# 3_DAC_schdoc.net
KiCad netlist of a schematic drawn in Altium Designer
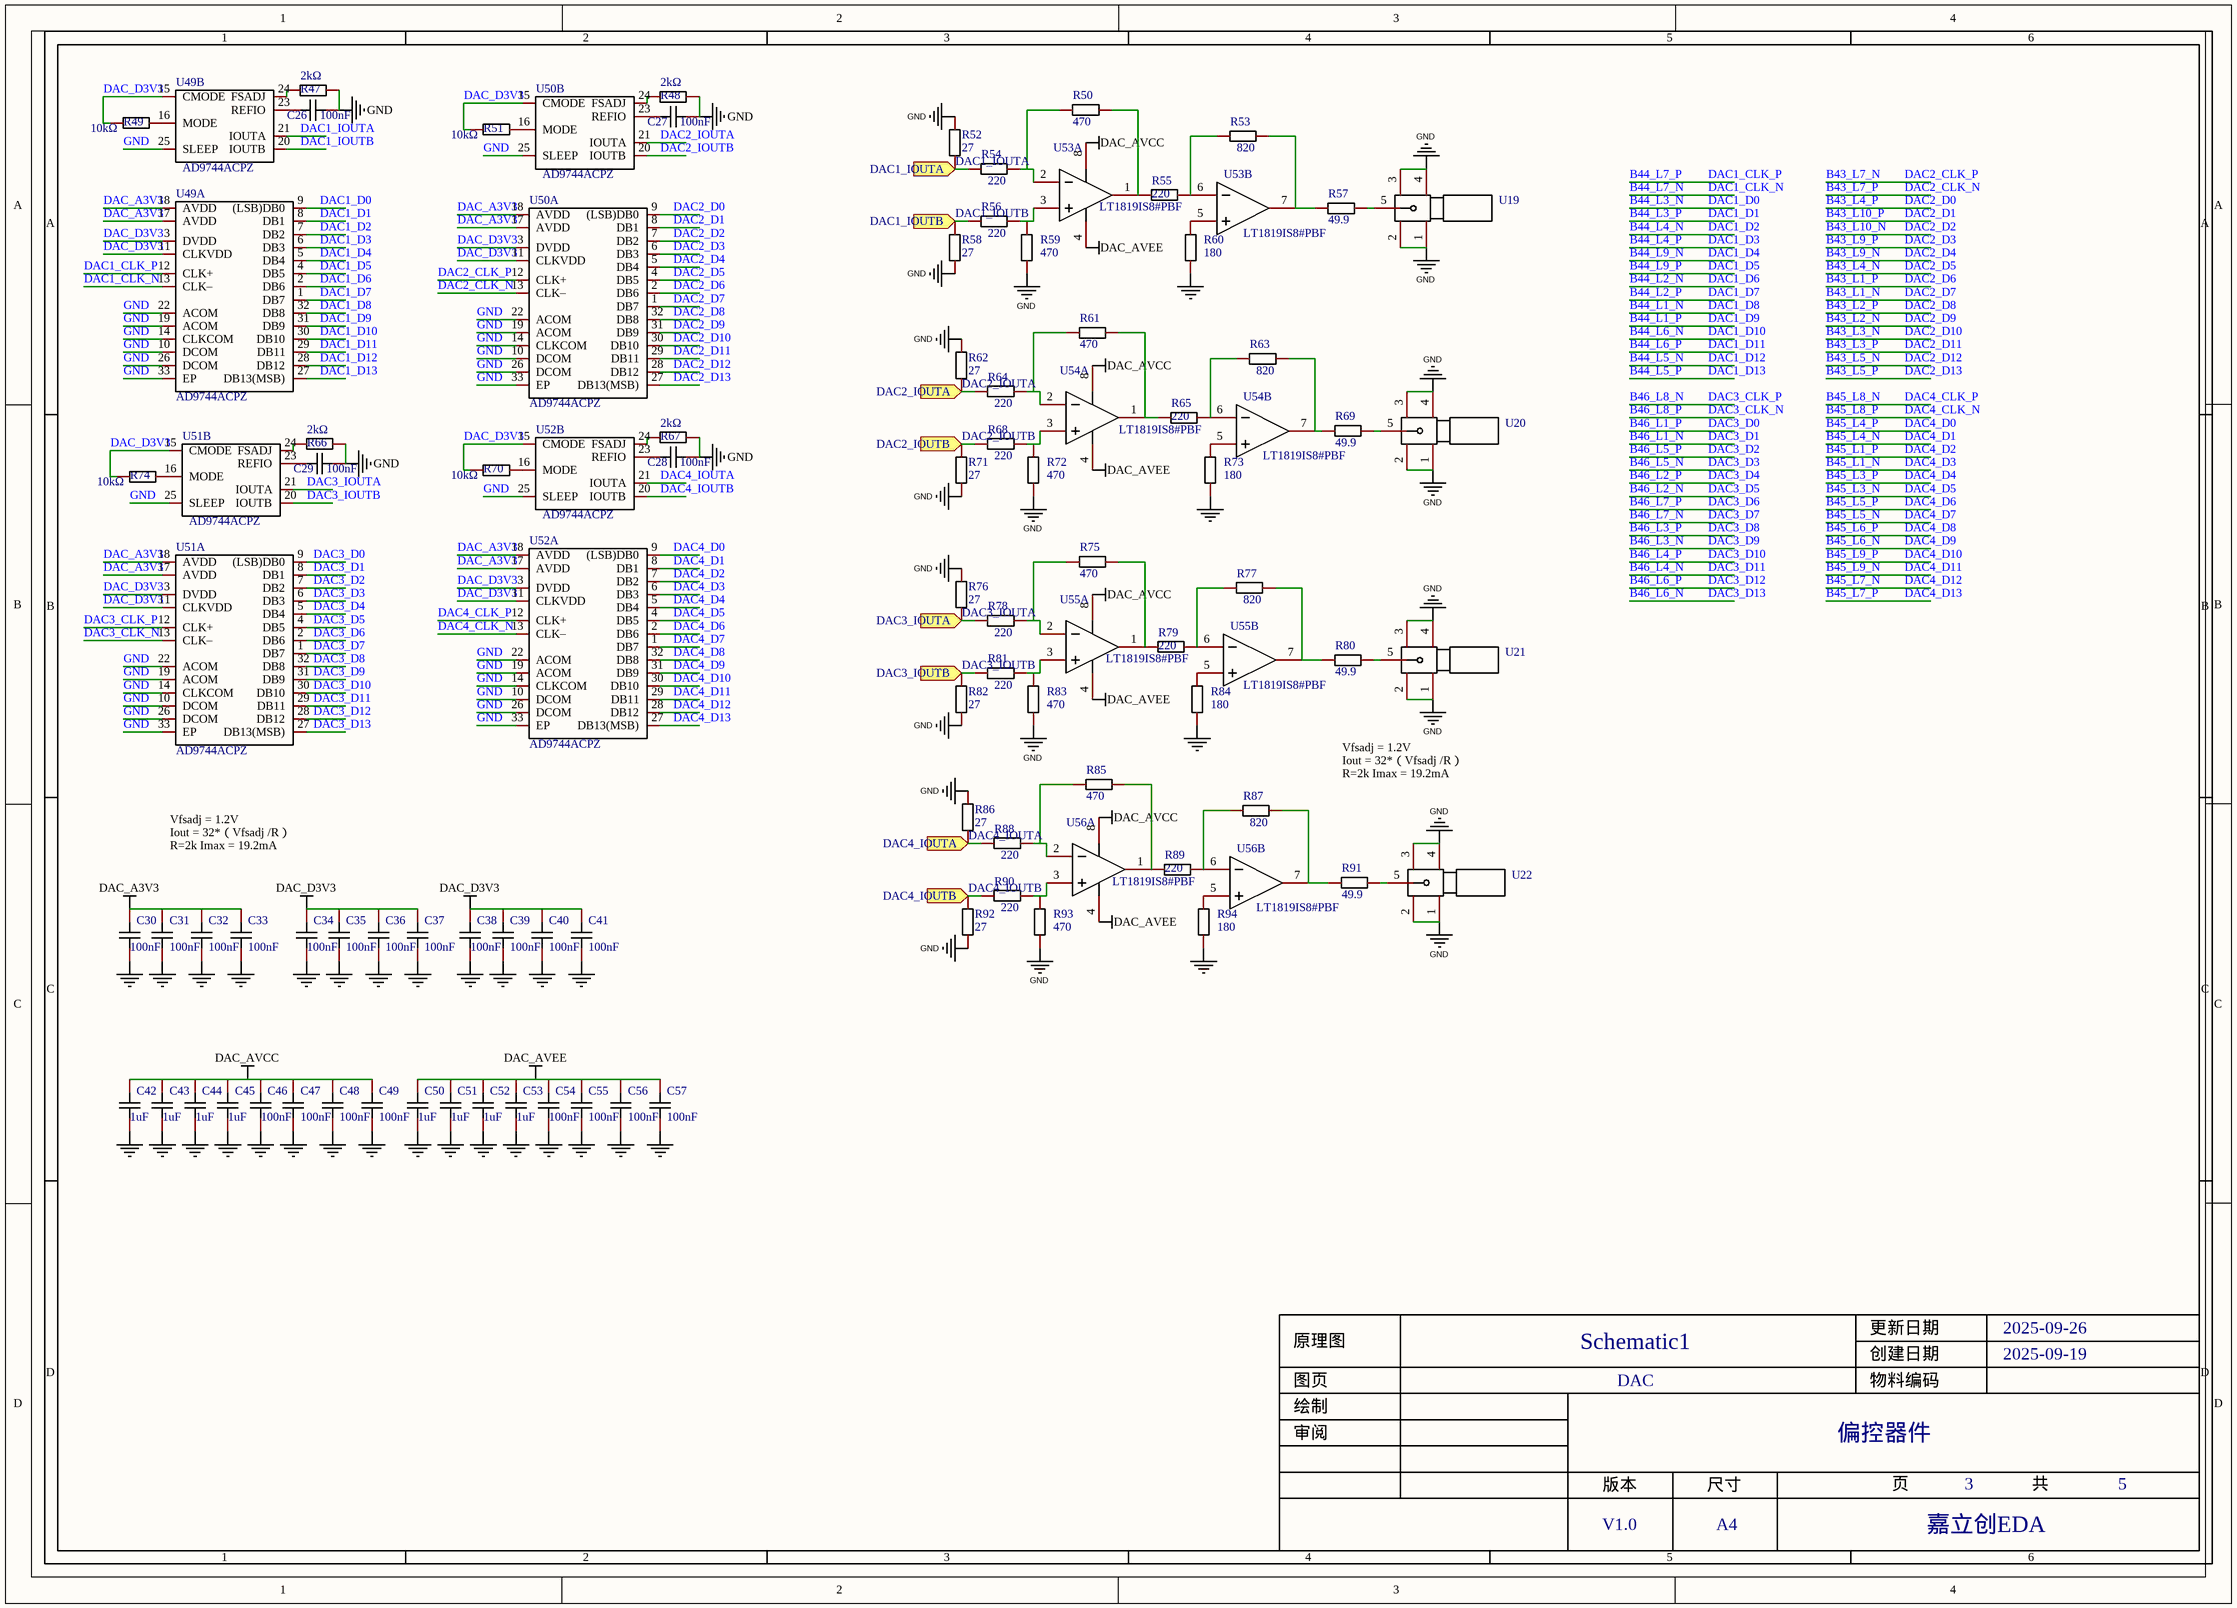
[diagram p0: 3_DAC.schdoc.schdoc]

(export (version "E")
  (design (tool "Eeschema 10.0.6"))
  (components
    (comp (ref "C26")
      (value "100nF")
      (fields
        (field (name "NAME") "100nF")
        (field (name "MANUFACTURER") "muRata(村田)")
        (field (name "MANUFACTURER PART") "GRM155R71H104KE14D")
        (field (name "TOLERANCE") "±10%")
      )
      (libsource (lib "altium-import") (part "root_0_GRM155R71H104KE14D_"))
    )
    (comp (ref "C27")
      (value "100nF")
      (fields
        (field (name "NAME") "100nF")
        (field (name "MANUFACTURER") "muRata(村田)")
        (field (name "MANUFACTURER PART") "GRM155R71H104KE14D")
        (field (name "TOLERANCE") "±10%")
      )
      (libsource (lib "altium-import") (part "root_0_GRM155R71H104KE14D_"))
    )
    (comp (ref "C28")
      (value "100nF")
      (fields
        (field (name "NAME") "100nF")
        (field (name "MANUFACTURER") "muRata(村田)")
        (field (name "MANUFACTURER PART") "GRM155R71H104KE14D")
        (field (name "TOLERANCE") "±10%")
      )
      (libsource (lib "altium-import") (part "root_0_GRM155R71H104KE14D_"))
    )
    (comp (ref "C29")
      (value "100nF")
      (fields
        (field (name "NAME") "100nF")
        (field (name "MANUFACTURER") "muRata(村田)")
        (field (name "MANUFACTURER PART") "GRM155R71H104KE14D")
        (field (name "TOLERANCE") "±10%")
      )
      (libsource (lib "altium-import") (part "root_0_GRM155R71H104KE14D_"))
    )
    (comp (ref "C30")
      (value "100nF")
      (fields
        (field (name "NAME") "100nF")
        (field (name "MANUFACTURER") "muRata(村田)")
        (field (name "MANUFACTURER PART") "GRM155R71H104KE14D")
        (field (name "TOLERANCE") "±10%")
      )
      (libsource (lib "altium-import") (part "root_1_GRM155R71H104KE14D_"))
    )
    (comp (ref "C31")
      (value "100nF")
      (fields
        (field (name "NAME") "100nF")
        (field (name "MANUFACTURER") "muRata(村田)")
        (field (name "MANUFACTURER PART") "GRM155R71H104KE14D")
        (field (name "TOLERANCE") "±10%")
      )
      (libsource (lib "altium-import") (part "root_1_GRM155R71H104KE14D_"))
    )
    (comp (ref "C32")
      (value "100nF")
      (fields
        (field (name "NAME") "100nF")
        (field (name "MANUFACTURER") "muRata(村田)")
        (field (name "MANUFACTURER PART") "GRM155R71H104KE14D")
        (field (name "TOLERANCE") "±10%")
      )
      (libsource (lib "altium-import") (part "root_1_GRM155R71H104KE14D_"))
    )
    (comp (ref "C33")
      (value "100nF")
      (fields
        (field (name "NAME") "100nF")
        (field (name "MANUFACTURER") "muRata(村田)")
        (field (name "MANUFACTURER PART") "GRM155R71H104KE14D")
        (field (name "TOLERANCE") "±10%")
      )
      (libsource (lib "altium-import") (part "root_1_GRM155R71H104KE14D_"))
    )
    (comp (ref "C34")
      (value "100nF")
      (fields
        (field (name "NAME") "100nF")
        (field (name "MANUFACTURER") "muRata(村田)")
        (field (name "MANUFACTURER PART") "GRM155R71H104KE14D")
        (field (name "TOLERANCE") "±10%")
      )
      (libsource (lib "altium-import") (part "root_1_GRM155R71H104KE14D_"))
    )
    (comp (ref "C35")
      (value "100nF")
      (fields
        (field (name "NAME") "100nF")
        (field (name "MANUFACTURER") "muRata(村田)")
        (field (name "MANUFACTURER PART") "GRM155R71H104KE14D")
        (field (name "TOLERANCE") "±10%")
      )
      (libsource (lib "altium-import") (part "root_1_GRM155R71H104KE14D_"))
    )
    (comp (ref "C36")
      (value "100nF")
      (fields
        (field (name "NAME") "100nF")
        (field (name "MANUFACTURER") "muRata(村田)")
        (field (name "MANUFACTURER PART") "GRM155R71H104KE14D")
        (field (name "TOLERANCE") "±10%")
      )
      (libsource (lib "altium-import") (part "root_1_GRM155R71H104KE14D_"))
    )
    (comp (ref "C37")
      (value "100nF")
      (fields
        (field (name "NAME") "100nF")
        (field (name "MANUFACTURER") "muRata(村田)")
        (field (name "MANUFACTURER PART") "GRM155R71H104KE14D")
        (field (name "TOLERANCE") "±10%")
      )
      (libsource (lib "altium-import") (part "root_1_GRM155R71H104KE14D_"))
    )
    (comp (ref "C38")
      (value "100nF")
      (fields
        (field (name "NAME") "100nF")
        (field (name "MANUFACTURER") "muRata(村田)")
        (field (name "MANUFACTURER PART") "GRM155R71H104KE14D")
        (field (name "TOLERANCE") "±10%")
      )
      (libsource (lib "altium-import") (part "root_1_GRM155R71H104KE14D_"))
    )
    (comp (ref "C39")
      (value "100nF")
      (fields
        (field (name "NAME") "100nF")
        (field (name "MANUFACTURER") "muRata(村田)")
        (field (name "MANUFACTURER PART") "GRM155R71H104KE14D")
        (field (name "TOLERANCE") "±10%")
      )
      (libsource (lib "altium-import") (part "root_1_GRM155R71H104KE14D_"))
    )
    (comp (ref "C40")
      (value "100nF")
      (fields
        (field (name "NAME") "100nF")
        (field (name "MANUFACTURER") "muRata(村田)")
        (field (name "MANUFACTURER PART") "GRM155R71H104KE14D")
        (field (name "TOLERANCE") "±10%")
      )
      (libsource (lib "altium-import") (part "root_1_GRM155R71H104KE14D_"))
    )
    (comp (ref "C41")
      (value "100nF")
      (fields
        (field (name "NAME") "100nF")
        (field (name "MANUFACTURER") "muRata(村田)")
        (field (name "MANUFACTURER PART") "GRM155R71H104KE14D")
        (field (name "TOLERANCE") "±10%")
      )
      (libsource (lib "altium-import") (part "root_1_GRM155R71H104KE14D_"))
    )
    (comp (ref "C42")
      (value "1uF")
      (fields
        (field (name "NAME") "1uF")
        (field (name "MANUFACTURER") "YAGEO(国巨)")
        (field (name "MANUFACTURER PART") "CC0603KRX7R9BB105")
        (field (name "TOLERANCE") "±10%")
      )
      (libsource (lib "altium-import") (part "root_1_CC0603KRX7R9BB105_"))
    )
    (comp (ref "C43")
      (value "1uF")
      (fields
        (field (name "NAME") "1uF")
        (field (name "MANUFACTURER") "YAGEO(国巨)")
        (field (name "MANUFACTURER PART") "CC0603KRX7R9BB105")
        (field (name "TOLERANCE") "±10%")
      )
      (libsource (lib "altium-import") (part "root_1_CC0603KRX7R9BB105_"))
    )
    (comp (ref "C44")
      (value "1uF")
      (fields
        (field (name "NAME") "1uF")
        (field (name "MANUFACTURER") "YAGEO(国巨)")
        (field (name "MANUFACTURER PART") "CC0603KRX7R9BB105")
        (field (name "TOLERANCE") "±10%")
      )
      (libsource (lib "altium-import") (part "root_1_CC0603KRX7R9BB105_"))
    )
    (comp (ref "C45")
      (value "1uF")
      (fields
        (field (name "NAME") "1uF")
        (field (name "MANUFACTURER") "YAGEO(国巨)")
        (field (name "MANUFACTURER PART") "CC0603KRX7R9BB105")
        (field (name "TOLERANCE") "±10%")
      )
      (libsource (lib "altium-import") (part "root_1_CC0603KRX7R9BB105_"))
    )
    (comp (ref "C46")
      (value "100nF")
      (fields
        (field (name "NAME") "100nF")
        (field (name "MANUFACTURER") "muRata(村田)")
        (field (name "MANUFACTURER PART") "GRM155R71H104KE14D")
        (field (name "TOLERANCE") "±10%")
      )
      (libsource (lib "altium-import") (part "root_1_GRM155R71H104KE14D_"))
    )
    (comp (ref "C47")
      (value "100nF")
      (fields
        (field (name "NAME") "100nF")
        (field (name "MANUFACTURER") "muRata(村田)")
        (field (name "MANUFACTURER PART") "GRM155R71H104KE14D")
        (field (name "TOLERANCE") "±10%")
      )
      (libsource (lib "altium-import") (part "root_1_GRM155R71H104KE14D_"))
    )
    (comp (ref "C48")
      (value "100nF")
      (fields
        (field (name "NAME") "100nF")
        (field (name "MANUFACTURER") "muRata(村田)")
        (field (name "MANUFACTURER PART") "GRM155R71H104KE14D")
        (field (name "TOLERANCE") "±10%")
      )
      (libsource (lib "altium-import") (part "root_1_GRM155R71H104KE14D_"))
    )
    (comp (ref "C49")
      (value "100nF")
      (fields
        (field (name "NAME") "100nF")
        (field (name "MANUFACTURER") "muRata(村田)")
        (field (name "MANUFACTURER PART") "GRM155R71H104KE14D")
        (field (name "TOLERANCE") "±10%")
      )
      (libsource (lib "altium-import") (part "root_1_GRM155R71H104KE14D_"))
    )
    (comp (ref "C50")
      (value "1uF")
      (fields
        (field (name "NAME") "1uF")
        (field (name "MANUFACTURER") "YAGEO(国巨)")
        (field (name "MANUFACTURER PART") "CC0603KRX7R9BB105")
        (field (name "TOLERANCE") "±10%")
      )
      (libsource (lib "altium-import") (part "root_1_CC0603KRX7R9BB105_"))
    )
    (comp (ref "C51")
      (value "1uF")
      (fields
        (field (name "NAME") "1uF")
        (field (name "MANUFACTURER") "YAGEO(国巨)")
        (field (name "MANUFACTURER PART") "CC0603KRX7R9BB105")
        (field (name "TOLERANCE") "±10%")
      )
      (libsource (lib "altium-import") (part "root_1_CC0603KRX7R9BB105_"))
    )
    (comp (ref "C52")
      (value "1uF")
      (fields
        (field (name "NAME") "1uF")
        (field (name "MANUFACTURER") "YAGEO(国巨)")
        (field (name "MANUFACTURER PART") "CC0603KRX7R9BB105")
        (field (name "TOLERANCE") "±10%")
      )
      (libsource (lib "altium-import") (part "root_1_CC0603KRX7R9BB105_"))
    )
    (comp (ref "C53")
      (value "1uF")
      (fields
        (field (name "NAME") "1uF")
        (field (name "MANUFACTURER") "YAGEO(国巨)")
        (field (name "MANUFACTURER PART") "CC0603KRX7R9BB105")
        (field (name "TOLERANCE") "±10%")
      )
      (libsource (lib "altium-import") (part "root_1_CC0603KRX7R9BB105_"))
    )
    (comp (ref "C54")
      (value "100nF")
      (fields
        (field (name "NAME") "100nF")
        (field (name "MANUFACTURER") "muRata(村田)")
        (field (name "MANUFACTURER PART") "GRM155R71H104KE14D")
        (field (name "TOLERANCE") "±10%")
      )
      (libsource (lib "altium-import") (part "root_1_GRM155R71H104KE14D_"))
    )
    (comp (ref "C55")
      (value "100nF")
      (fields
        (field (name "NAME") "100nF")
        (field (name "MANUFACTURER") "muRata(村田)")
        (field (name "MANUFACTURER PART") "GRM155R71H104KE14D")
        (field (name "TOLERANCE") "±10%")
      )
      (libsource (lib "altium-import") (part "root_1_GRM155R71H104KE14D_"))
    )
    (comp (ref "C56")
      (value "100nF")
      (fields
        (field (name "NAME") "100nF")
        (field (name "MANUFACTURER") "muRata(村田)")
        (field (name "MANUFACTURER PART") "GRM155R71H104KE14D")
        (field (name "TOLERANCE") "±10%")
      )
      (libsource (lib "altium-import") (part "root_1_GRM155R71H104KE14D_"))
    )
    (comp (ref "C57")
      (value "100nF")
      (fields
        (field (name "NAME") "100nF")
        (field (name "MANUFACTURER") "muRata(村田)")
        (field (name "MANUFACTURER PART") "GRM155R71H104KE14D")
        (field (name "TOLERANCE") "±10%")
      )
      (libsource (lib "altium-import") (part "root_1_GRM155R71H104KE14D_"))
    )
    (comp (ref "R47")
      (value "2kΩ")
      (fields
        (field (name "NAME") "2kΩ")
        (field (name "MANUFACTURER") "UNI-ROYAL(厚声)")
        (field (name "MANUFACTURER PART") "0402WGF1001TCE")
        (field (name "TOLERANCE") "±1%")
      )
      (libsource (lib "altium-import") (part "root_0_0402WGF1001TCE_"))
    )
    (comp (ref "R48")
      (value "2kΩ")
      (fields
        (field (name "NAME") "2kΩ")
        (field (name "MANUFACTURER") "UNI-ROYAL(厚声)")
        (field (name "MANUFACTURER PART") "0402WGF1001TCE")
        (field (name "TOLERANCE") "±1%")
      )
      (libsource (lib "altium-import") (part "root_0_0402WGF1001TCE_"))
    )
    (comp (ref "R49")
      (value "10kΩ")
      (fields
        (field (name "NAME") "10kΩ")
        (field (name "MANUFACTURER") "UNI-ROYAL(厚声)")
        (field (name "MANUFACTURER PART") "0402WGF1001TCE")
        (field (name "TOLERANCE") "±1%")
      )
      (libsource (lib "altium-import") (part "root_2_0402WGF1001TCE_"))
    )
    (comp (ref "R50")
      (value "470")
      (fields (field (name "NAME") "470"))
      (libsource (lib "altium-import") (part "root_2_Res_0402_"))
    )
    (comp (ref "R51")
      (value "10kΩ")
      (fields
        (field (name "NAME") "10kΩ")
        (field (name "MANUFACTURER") "UNI-ROYAL(厚声)")
        (field (name "MANUFACTURER PART") "0402WGF1001TCE")
        (field (name "TOLERANCE") "±1%")
      )
      (libsource (lib "altium-import") (part "root_2_0402WGF1001TCE_"))
    )
    (comp (ref "R52")
      (value "27")
      (fields (field (name "NAME") "27"))
      (libsource (lib "altium-import") (part "root_1_Res_0402_"))
    )
    (comp (ref "R53")
      (value "820")
      (fields (field (name "NAME") "820"))
      (libsource (lib "altium-import") (part "root_2_Res_0402_"))
    )
    (comp (ref "R54")
      (value "220")
      (fields (field (name "NAME") "220"))
      (libsource (lib "altium-import") (part "root_2_Res_0402_"))
    )
    (comp (ref "R55")
      (value "220")
      (fields (field (name "NAME") "220"))
      (libsource (lib "altium-import") (part "root_2_Res_0402_"))
    )
    (comp (ref "R56")
      (value "220")
      (fields (field (name "NAME") "220"))
      (libsource (lib "altium-import") (part "root_2_Res_0402_"))
    )
    (comp (ref "R57")
      (value "49.9")
      (fields (field (name "NAME") "49.9"))
      (libsource (lib "altium-import") (part "root_0_Res_0603_"))
    )
    (comp (ref "R58")
      (value "27")
      (fields (field (name "NAME") "27"))
      (libsource (lib "altium-import") (part "root_1_Res_0402_"))
    )
    (comp (ref "R59")
      (value "470")
      (fields (field (name "NAME") "470"))
      (libsource (lib "altium-import") (part "root_3_Res_0402_"))
    )
    (comp (ref "R60")
      (value "180")
      (fields (field (name "NAME") "180"))
      (libsource (lib "altium-import") (part "root_3_Res_0402_"))
    )
    (comp (ref "R61")
      (value "470")
      (fields (field (name "NAME") "470"))
      (libsource (lib "altium-import") (part "root_2_Res_0402_"))
    )
    (comp (ref "R62")
      (value "27")
      (fields (field (name "NAME") "27"))
      (libsource (lib "altium-import") (part "root_1_Res_0402_"))
    )
    (comp (ref "R63")
      (value "820")
      (fields (field (name "NAME") "820"))
      (libsource (lib "altium-import") (part "root_2_Res_0402_"))
    )
    (comp (ref "R64")
      (value "220")
      (fields (field (name "NAME") "220"))
      (libsource (lib "altium-import") (part "root_2_Res_0402_"))
    )
    (comp (ref "R65")
      (value "220")
      (fields (field (name "NAME") "220"))
      (libsource (lib "altium-import") (part "root_2_Res_0402_"))
    )
    (comp (ref "R66")
      (value "2kΩ")
      (fields
        (field (name "NAME") "2kΩ")
        (field (name "MANUFACTURER") "UNI-ROYAL(厚声)")
        (field (name "MANUFACTURER PART") "0402WGF1001TCE")
        (field (name "TOLERANCE") "±1%")
      )
      (libsource (lib "altium-import") (part "root_0_0402WGF1001TCE_"))
    )
    (comp (ref "R67")
      (value "2kΩ")
      (fields
        (field (name "NAME") "2kΩ")
        (field (name "MANUFACTURER") "UNI-ROYAL(厚声)")
        (field (name "MANUFACTURER PART") "0402WGF1001TCE")
        (field (name "TOLERANCE") "±1%")
      )
      (libsource (lib "altium-import") (part "root_0_0402WGF1001TCE_"))
    )
    (comp (ref "R68")
      (value "220")
      (fields (field (name "NAME") "220"))
      (libsource (lib "altium-import") (part "root_2_Res_0402_"))
    )
    (comp (ref "R69")
      (value "49.9")
      (fields (field (name "NAME") "49.9"))
      (libsource (lib "altium-import") (part "root_0_Res_0603_"))
    )
    (comp (ref "R70")
      (value "10kΩ")
      (fields
        (field (name "NAME") "10kΩ")
        (field (name "MANUFACTURER") "UNI-ROYAL(厚声)")
        (field (name "MANUFACTURER PART") "0402WGF1001TCE")
        (field (name "TOLERANCE") "±1%")
      )
      (libsource (lib "altium-import") (part "root_2_0402WGF1001TCE_"))
    )
    (comp (ref "R71")
      (value "27")
      (fields (field (name "NAME") "27"))
      (libsource (lib "altium-import") (part "root_1_Res_0402_"))
    )
    (comp (ref "R72")
      (value "470")
      (fields (field (name "NAME") "470"))
      (libsource (lib "altium-import") (part "root_3_Res_0402_"))
    )
    (comp (ref "R73")
      (value "180")
      (fields (field (name "NAME") "180"))
      (libsource (lib "altium-import") (part "root_3_Res_0402_"))
    )
    (comp (ref "R74")
      (value "10kΩ")
      (fields
        (field (name "NAME") "10kΩ")
        (field (name "MANUFACTURER") "UNI-ROYAL(厚声)")
        (field (name "MANUFACTURER PART") "0402WGF1001TCE")
        (field (name "TOLERANCE") "±1%")
      )
      (libsource (lib "altium-import") (part "root_2_0402WGF1001TCE_"))
    )
    (comp (ref "R75")
      (value "470")
      (fields (field (name "NAME") "470"))
      (libsource (lib "altium-import") (part "root_2_Res_0402_"))
    )
    (comp (ref "R76")
      (value "27")
      (fields (field (name "NAME") "27"))
      (libsource (lib "altium-import") (part "root_1_Res_0402_"))
    )
    (comp (ref "R77")
      (value "820")
      (fields (field (name "NAME") "820"))
      (libsource (lib "altium-import") (part "root_2_Res_0402_"))
    )
    (comp (ref "R78")
      (value "220")
      (fields (field (name "NAME") "220"))
      (libsource (lib "altium-import") (part "root_2_Res_0402_"))
    )
    (comp (ref "R79")
      (value "220")
      (fields (field (name "NAME") "220"))
      (libsource (lib "altium-import") (part "root_2_Res_0402_"))
    )
    (comp (ref "R80")
      (value "49.9")
      (fields (field (name "NAME") "49.9"))
      (libsource (lib "altium-import") (part "root_0_Res_0603_"))
    )
    (comp (ref "R81")
      (value "220")
      (fields (field (name "NAME") "220"))
      (libsource (lib "altium-import") (part "root_2_Res_0402_"))
    )
    (comp (ref "R82")
      (value "27")
      (fields (field (name "NAME") "27"))
      (libsource (lib "altium-import") (part "root_1_Res_0402_"))
    )
    (comp (ref "R83")
      (value "470")
      (fields (field (name "NAME") "470"))
      (libsource (lib "altium-import") (part "root_3_Res_0402_"))
    )
    (comp (ref "R84")
      (value "180")
      (fields (field (name "NAME") "180"))
      (libsource (lib "altium-import") (part "root_3_Res_0402_"))
    )
    (comp (ref "R85")
      (value "470")
      (fields (field (name "NAME") "470"))
      (libsource (lib "altium-import") (part "root_2_Res_0402_"))
    )
    (comp (ref "R86")
      (value "27")
      (fields (field (name "NAME") "27"))
      (libsource (lib "altium-import") (part "root_1_Res_0402_"))
    )
    (comp (ref "R87")
      (value "820")
      (fields (field (name "NAME") "820"))
      (libsource (lib "altium-import") (part "root_2_Res_0402_"))
    )
    (comp (ref "R88")
      (value "220")
      (fields (field (name "NAME") "220"))
      (libsource (lib "altium-import") (part "root_2_Res_0402_"))
    )
    (comp (ref "R89")
      (value "220")
      (fields (field (name "NAME") "220"))
      (libsource (lib "altium-import") (part "root_2_Res_0402_"))
    )
    (comp (ref "R90")
      (value "220")
      (fields (field (name "NAME") "220"))
      (libsource (lib "altium-import") (part "root_2_Res_0402_"))
    )
    (comp (ref "R91")
      (value "49.9")
      (fields (field (name "NAME") "49.9"))
      (libsource (lib "altium-import") (part "root_0_Res_0603_"))
    )
    (comp (ref "R92")
      (value "27")
      (fields (field (name "NAME") "27"))
      (libsource (lib "altium-import") (part "root_1_Res_0402_"))
    )
    (comp (ref "R93")
      (value "470")
      (fields (field (name "NAME") "470"))
      (libsource (lib "altium-import") (part "root_3_Res_0402_"))
    )
    (comp (ref "R94")
      (value "180")
      (fields (field (name "NAME") "180"))
      (libsource (lib "altium-import") (part "root_3_Res_0402_"))
    )
    (comp (ref "U19")
      (value "MOLEX_SMA")
      (description "C296128")
      (libsource (lib "altium-import") (part "root_2_MOLEX_SMA_"))
    )
    (comp (ref "U20")
      (value "MOLEX_SMA")
      (description "C296128")
      (libsource (lib "altium-import") (part "root_2_MOLEX_SMA_"))
    )
    (comp (ref "U21")
      (value "MOLEX_SMA")
      (description "C296128")
      (libsource (lib "altium-import") (part "root_2_MOLEX_SMA_"))
    )
    (comp (ref "U22")
      (value "MOLEX_SMA")
      (description "C296128")
      (libsource (lib "altium-import") (part "root_2_MOLEX_SMA_"))
    )
    (comp (ref "U49")
      (value "AD9744ACPZ")
      (description "接口:并行;分辨率:14位;稳定时间:11ns;INL/DNL:±0.5LSB；±0.8LSB;电源电压:2.7V~3.6V;")
      (fields (field (name "NAME") "AD9744ACPZ") (field (name "MANUFACTURER") "ADI(亚德诺)"))
      (libsource (lib "altium-import") (part "root_0_AD9744ACPZ_"))
    )
    (comp (ref "U50")
      (value "AD9744ACPZ")
      (description "接口:并行;分辨率:14位;稳定时间:11ns;INL/DNL:±0.5LSB；±0.8LSB;电源电压:2.7V~3.6V;")
      (fields (field (name "NAME") "AD9744ACPZ") (field (name "MANUFACTURER") "ADI(亚德诺)"))
      (libsource (lib "altium-import") (part "root_0_AD9744ACPZ_"))
    )
    (comp (ref "U51")
      (value "AD9744ACPZ")
      (description "接口:并行;分辨率:14位;稳定时间:11ns;INL/DNL:±0.5LSB；±0.8LSB;电源电压:2.7V~3.6V;")
      (fields (field (name "NAME") "AD9744ACPZ") (field (name "MANUFACTURER") "ADI(亚德诺)"))
      (libsource (lib "altium-import") (part "root_0_AD9744ACPZ_"))
    )
    (comp (ref "U52")
      (value "AD9744ACPZ")
      (description "接口:并行;分辨率:14位;稳定时间:11ns;INL/DNL:±0.5LSB；±0.8LSB;电源电压:2.7V~3.6V;")
      (fields (field (name "NAME") "AD9744ACPZ") (field (name "MANUFACTURER") "ADI(亚德诺)"))
      (libsource (lib "altium-import") (part "root_0_AD9744ACPZ_"))
    )
    (comp (ref "U53")
      (value "LT1819IS8#PBF")
      (description "放大器数:双路;轨到轨:-;增益带宽积(GBP):400MHz;输入失调电压(Vos):1.5mV;压摆率(SR):2500V/us;输入偏置电流(Ib):2uA;")
      (fields (field (name "NAME") "LT1819IS8#PBF") (field (name "MANUFACTURER") "ADI(亚德诺)"))
      (libsource (lib "altium-import") (part "root_0_LT1819IS8#PBF_"))
    )
    (comp (ref "U54")
      (value "LT1819IS8#PBF")
      (description "放大器数:双路;轨到轨:-;增益带宽积(GBP):400MHz;输入失调电压(Vos):1.5mV;压摆率(SR):2500V/us;输入偏置电流(Ib):2uA;")
      (fields (field (name "NAME") "LT1819IS8#PBF") (field (name "MANUFACTURER") "ADI(亚德诺)"))
      (libsource (lib "altium-import") (part "root_0_LT1819IS8#PBF_"))
    )
    (comp (ref "U55")
      (value "LT1819IS8#PBF")
      (description "放大器数:双路;轨到轨:-;增益带宽积(GBP):400MHz;输入失调电压(Vos):1.5mV;压摆率(SR):2500V/us;输入偏置电流(Ib):2uA;")
      (fields (field (name "NAME") "LT1819IS8#PBF") (field (name "MANUFACTURER") "ADI(亚德诺)"))
      (libsource (lib "altium-import") (part "root_0_LT1819IS8#PBF_"))
    )
    (comp (ref "U56")
      (value "LT1819IS8#PBF")
      (description "放大器数:双路;轨到轨:-;增益带宽积(GBP):400MHz;输入失调电压(Vos):1.5mV;压摆率(SR):2500V/us;输入偏置电流(Ib):2uA;")
      (fields (field (name "NAME") "LT1819IS8#PBF") (field (name "MANUFACTURER") "ADI(亚德诺)"))
      (libsource (lib "altium-import") (part "root_0_LT1819IS8#PBF_"))
    )
  )
  (nets
    (net (code "1") (name "/B43_L1_N") (class "Default")
      (node (ref "U50") (pin "1") (pinfunction "DB7_1") (pintype "passive"))
    )
    (net (code "2") (name "/B43_L1_P") (class "Default")
      (node (ref "U50") (pin "2") (pinfunction "DB6_2") (pintype "passive"))
    )
    (net (code "3") (name "/B43_L2_N") (class "Default")
      (node (ref "U50") (pin "31") (pinfunction "DB9_31") (pintype "passive"))
    )
    (net (code "4") (name "/B43_L2_P") (class "Default")
      (node (ref "U50") (pin "32") (pinfunction "DB8_32") (pintype "passive"))
    )
    (net (code "5") (name "/B43_L3_N") (class "Default")
      (node (ref "U50") (pin "30") (pinfunction "DB10_30") (pintype "passive"))
    )
    (net (code "6") (name "/B43_L3_P") (class "Default")
      (node (ref "U50") (pin "29") (pinfunction "DB11_29") (pintype "passive"))
    )
    (net (code "7") (name "/B43_L4_N") (class "Default")
      (node (ref "U50") (pin "4") (pinfunction "DB5_4") (pintype "passive"))
    )
    (net (code "8") (name "/B43_L4_P") (class "Default")
      (node (ref "U50") (pin "9") (pinfunction "(LSB)DB0_9") (pintype "passive"))
    )
    (net (code "9") (name "/B43_L5_N") (class "Default")
      (node (ref "U50") (pin "28") (pinfunction "DB12_28") (pintype "passive"))
    )
    (net (code "10") (name "/B43_L5_P") (class "Default")
      (node (ref "U50") (pin "27") (pinfunction "DB13(MSB)_27") (pintype "passive"))
    )
    (net (code "11") (name "/B43_L7_N") (class "Default")
      (node (ref "U50") (pin "12") (pinfunction "CLK+_12") (pintype "passive"))
    )
    (net (code "12") (name "/B43_L7_P") (class "Default")
      (node (ref "U50") (pin "13") (pinfunction "CLK–_13") (pintype "passive"))
    )
    (net (code "13") (name "/B43_L9_N") (class "Default")
      (node (ref "U50") (pin "5") (pinfunction "DB4_5") (pintype "passive"))
    )
    (net (code "14") (name "/B43_L9_P") (class "Default")
      (node (ref "U50") (pin "6") (pinfunction "DB3_6") (pintype "passive"))
    )
    (net (code "15") (name "/B43_L10_N") (class "Default")
      (node (ref "U50") (pin "7") (pinfunction "DB2_7") (pintype "passive"))
    )
    (net (code "16") (name "/B43_L10_P") (class "Default")
      (node (ref "U50") (pin "8") (pinfunction "DB1_8") (pintype "passive"))
    )
    (net (code "17") (name "/B44_L1_N") (class "Default")
      (node (ref "U49") (pin "32") (pinfunction "DB8_32") (pintype "passive"))
    )
    (net (code "18") (name "/B44_L1_P") (class "Default")
      (node (ref "U49") (pin "31") (pinfunction "DB9_31") (pintype "passive"))
    )
    (net (code "19") (name "/B44_L2_N") (class "Default")
      (node (ref "U49") (pin "2") (pinfunction "DB6_2") (pintype "passive"))
    )
    (net (code "20") (name "/B44_L2_P") (class "Default")
      (node (ref "U49") (pin "1") (pinfunction "DB7_1") (pintype "passive"))
    )
    (net (code "21") (name "/B44_L3_N") (class "Default")
      (node (ref "U49") (pin "9") (pinfunction "(LSB)DB0_9") (pintype "passive"))
    )
    (net (code "22") (name "/B44_L3_P") (class "Default")
      (node (ref "U49") (pin "8") (pinfunction "DB1_8") (pintype "passive"))
    )
    (net (code "23") (name "/B44_L4_N") (class "Default")
      (node (ref "U49") (pin "7") (pinfunction "DB2_7") (pintype "passive"))
    )
    (net (code "24") (name "/B44_L4_P") (class "Default")
      (node (ref "U49") (pin "6") (pinfunction "DB3_6") (pintype "passive"))
    )
    (net (code "25") (name "/B44_L5_N") (class "Default")
      (node (ref "U49") (pin "28") (pinfunction "DB12_28") (pintype "passive"))
    )
    (net (code "26") (name "/B44_L5_P") (class "Default")
      (node (ref "U49") (pin "27") (pinfunction "DB13(MSB)_27") (pintype "passive"))
    )
    (net (code "27") (name "/B44_L6_N") (class "Default")
      (node (ref "U49") (pin "30") (pinfunction "DB10_30") (pintype "passive"))
    )
    (net (code "28") (name "/B44_L6_P") (class "Default")
      (node (ref "U49") (pin "29") (pinfunction "DB11_29") (pintype "passive"))
    )
    (net (code "29") (name "/B44_L7_N") (class "Default")
      (node (ref "U49") (pin "13") (pinfunction "CLK–_13") (pintype "passive"))
    )
    (net (code "30") (name "/B44_L7_P") (class "Default")
      (node (ref "U49") (pin "12") (pinfunction "CLK+_12") (pintype "passive"))
    )
    (net (code "31") (name "/B44_L9_N") (class "Default")
      (node (ref "U49") (pin "5") (pinfunction "DB4_5") (pintype "passive"))
    )
    (net (code "32") (name "/B44_L9_P") (class "Default")
      (node (ref "U49") (pin "4") (pinfunction "DB5_4") (pintype "passive"))
    )
    (net (code "33") (name "/B45_L1_N") (class "Default")
      (node (ref "U52") (pin "6") (pinfunction "DB3_6") (pintype "passive"))
    )
    (net (code "34") (name "/B45_L1_P") (class "Default")
      (node (ref "U52") (pin "7") (pinfunction "DB2_7") (pintype "passive"))
    )
    (net (code "35") (name "/B45_L3_N") (class "Default")
      (node (ref "U52") (pin "4") (pinfunction "DB5_4") (pintype "passive"))
    )
    (net (code "36") (name "/B45_L3_P") (class "Default")
      (node (ref "U52") (pin "5") (pinfunction "DB4_5") (pintype "passive"))
    )
    (net (code "37") (name "/B45_L4_N") (class "Default")
      (node (ref "U52") (pin "8") (pinfunction "DB1_8") (pintype "passive"))
    )
    (net (code "38") (name "/B45_L4_P") (class "Default")
      (node (ref "U52") (pin "9") (pinfunction "(LSB)DB0_9") (pintype "passive"))
    )
    (net (code "39") (name "/B45_L5_N") (class "Default")
      (node (ref "U52") (pin "1") (pinfunction "DB7_1") (pintype "passive"))
    )
    (net (code "40") (name "/B45_L5_P") (class "Default")
      (node (ref "U52") (pin "2") (pinfunction "DB6_2") (pintype "passive"))
    )
    (net (code "41") (name "/B45_L6_N") (class "Default")
      (node (ref "U52") (pin "31") (pinfunction "DB9_31") (pintype "passive"))
    )
    (net (code "42") (name "/B45_L6_P") (class "Default")
      (node (ref "U52") (pin "32") (pinfunction "DB8_32") (pintype "passive"))
    )
    (net (code "43") (name "/B45_L7_N") (class "Default")
      (node (ref "U52") (pin "28") (pinfunction "DB12_28") (pintype "passive"))
    )
    (net (code "44") (name "/B45_L7_P") (class "Default")
      (node (ref "U52") (pin "27") (pinfunction "DB13(MSB)_27") (pintype "passive"))
    )
    (net (code "45") (name "/B45_L8_N") (class "Default")
      (node (ref "U52") (pin "12") (pinfunction "CLK+_12") (pintype "passive"))
    )
    (net (code "46") (name "/B45_L8_P") (class "Default")
      (node (ref "U52") (pin "13") (pinfunction "CLK–_13") (pintype "passive"))
    )
    (net (code "47") (name "/B45_L9_N") (class "Default")
      (node (ref "U52") (pin "29") (pinfunction "DB11_29") (pintype "passive"))
    )
    (net (code "48") (name "/B45_L9_P") (class "Default")
      (node (ref "U52") (pin "30") (pinfunction "DB10_30") (pintype "passive"))
    )
    (net (code "49") (name "/B46_L1_N") (class "Default")
      (node (ref "U51") (pin "8") (pinfunction "DB1_8") (pintype "passive"))
    )
    (net (code "50") (name "/B46_L1_P") (class "Default")
      (node (ref "U51") (pin "9") (pinfunction "(LSB)DB0_9") (pintype "passive"))
    )
    (net (code "51") (name "/B46_L2_N") (class "Default")
      (node (ref "U51") (pin "4") (pinfunction "DB5_4") (pintype "passive"))
    )
    (net (code "52") (name "/B46_L2_P") (class "Default")
      (node (ref "U51") (pin "5") (pinfunction "DB4_5") (pintype "passive"))
    )
    (net (code "53") (name "/B46_L3_N") (class "Default")
      (node (ref "U51") (pin "31") (pinfunction "DB9_31") (pintype "passive"))
    )
    (net (code "54") (name "/B46_L3_P") (class "Default")
      (node (ref "U51") (pin "32") (pinfunction "DB8_32") (pintype "passive"))
    )
    (net (code "55") (name "/B46_L4_N") (class "Default")
      (node (ref "U51") (pin "29") (pinfunction "DB11_29") (pintype "passive"))
    )
    (net (code "56") (name "/B46_L4_P") (class "Default")
      (node (ref "U51") (pin "30") (pinfunction "DB10_30") (pintype "passive"))
    )
    (net (code "57") (name "/B46_L5_N") (class "Default")
      (node (ref "U51") (pin "6") (pinfunction "DB3_6") (pintype "passive"))
    )
    (net (code "58") (name "/B46_L5_P") (class "Default")
      (node (ref "U51") (pin "7") (pinfunction "DB2_7") (pintype "passive"))
    )
    (net (code "59") (name "/B46_L6_N") (class "Default")
      (node (ref "U51") (pin "27") (pinfunction "DB13(MSB)_27") (pintype "passive"))
    )
    (net (code "60") (name "/B46_L6_P") (class "Default")
      (node (ref "U51") (pin "28") (pinfunction "DB12_28") (pintype "passive"))
    )
    (net (code "61") (name "/B46_L7_N") (class "Default")
      (node (ref "U51") (pin "1") (pinfunction "DB7_1") (pintype "passive"))
    )
    (net (code "62") (name "/B46_L7_P") (class "Default")
      (node (ref "U51") (pin "2") (pinfunction "DB6_2") (pintype "passive"))
    )
    (net (code "63") (name "/B46_L8_N") (class "Default")
      (node (ref "U51") (pin "12") (pinfunction "CLK+_12") (pintype "passive"))
    )
    (net (code "64") (name "/B46_L8_P") (class "Default")
      (node (ref "U51") (pin "13") (pinfunction "CLK–_13") (pintype "passive"))
    )
    (net (code "65") (name "/DAC1_IOUTA") (class "Default")
      (node (ref "R52") (pin "1") (pinfunction "1_1") (pintype "passive"))
      (node (ref "R54") (pin "2") (pinfunction "2_2") (pintype "passive"))
      (node (ref "U49") (pin "21") (pinfunction "IOUTA_21") (pintype "passive"))
    )
    (net (code "66") (name "/DAC1_IOUTB") (class "Default")
      (node (ref "R56") (pin "2") (pinfunction "2_2") (pintype "passive"))
      (node (ref "R58") (pin "2") (pinfunction "2_2") (pintype "passive"))
      (node (ref "U49") (pin "20") (pinfunction "IOUTB_20") (pintype "passive"))
    )
    (net (code "67") (name "/DAC2_IOUTA") (class "Default")
      (node (ref "R62") (pin "1") (pinfunction "1_1") (pintype "passive"))
      (node (ref "R64") (pin "2") (pinfunction "2_2") (pintype "passive"))
      (node (ref "U50") (pin "21") (pinfunction "IOUTA_21") (pintype "passive"))
    )
    (net (code "68") (name "/DAC2_IOUTB") (class "Default")
      (node (ref "R68") (pin "2") (pinfunction "2_2") (pintype "passive"))
      (node (ref "R71") (pin "2") (pinfunction "2_2") (pintype "passive"))
      (node (ref "U50") (pin "20") (pinfunction "IOUTB_20") (pintype "passive"))
    )
    (net (code "69") (name "/DAC3_IOUTA") (class "Default")
      (node (ref "R76") (pin "1") (pinfunction "1_1") (pintype "passive"))
      (node (ref "R78") (pin "2") (pinfunction "2_2") (pintype "passive"))
      (node (ref "U51") (pin "21") (pinfunction "IOUTA_21") (pintype "passive"))
    )
    (net (code "70") (name "/DAC3_IOUTB") (class "Default")
      (node (ref "R81") (pin "2") (pinfunction "2_2") (pintype "passive"))
      (node (ref "R82") (pin "2") (pinfunction "2_2") (pintype "passive"))
      (node (ref "U51") (pin "20") (pinfunction "IOUTB_20") (pintype "passive"))
    )
    (net (code "71") (name "/DAC4_IOUTA") (class "Default")
      (node (ref "R86") (pin "1") (pinfunction "1_1") (pintype "passive"))
      (node (ref "R88") (pin "2") (pinfunction "2_2") (pintype "passive"))
      (node (ref "U52") (pin "21") (pinfunction "IOUTA_21") (pintype "passive"))
    )
    (net (code "72") (name "/DAC4_IOUTB") (class "Default")
      (node (ref "R90") (pin "2") (pinfunction "2_2") (pintype "passive"))
      (node (ref "R92") (pin "2") (pinfunction "2_2") (pintype "passive"))
      (node (ref "U52") (pin "20") (pinfunction "IOUTB_20") (pintype "passive"))
    )
    (net (code "73") (name "DAC_A3V3") (class "Default")
      (node (ref "C30") (pin "2") (pinfunction "2_2") (pintype "passive"))
      (node (ref "C31") (pin "2") (pinfunction "2_2") (pintype "passive"))
      (node (ref "C32") (pin "2") (pinfunction "2_2") (pintype "passive"))
      (node (ref "C33") (pin "2") (pinfunction "2_2") (pintype "passive"))
      (node (ref "U49") (pin "17") (pinfunction "AVDD_17") (pintype "passive"))
      (node (ref "U49") (pin "18") (pinfunction "AVDD_18") (pintype "passive"))
      (node (ref "U50") (pin "17") (pinfunction "AVDD_17") (pintype "passive"))
      (node (ref "U50") (pin "18") (pinfunction "AVDD_18") (pintype "passive"))
      (node (ref "U51") (pin "17") (pinfunction "AVDD_17") (pintype "passive"))
      (node (ref "U51") (pin "18") (pinfunction "AVDD_18") (pintype "passive"))
      (node (ref "U52") (pin "17") (pinfunction "AVDD_17") (pintype "passive"))
      (node (ref "U52") (pin "18") (pinfunction "AVDD_18") (pintype "passive"))
    )
    (net (code "74") (name "DAC_AVCC") (class "Default")
      (node (ref "C42") (pin "2") (pinfunction "2_2") (pintype "passive"))
      (node (ref "C43") (pin "2") (pinfunction "2_2") (pintype "passive"))
      (node (ref "C44") (pin "2") (pinfunction "2_2") (pintype "passive"))
      (node (ref "C45") (pin "2") (pinfunction "2_2") (pintype "passive"))
      (node (ref "C46") (pin "2") (pinfunction "2_2") (pintype "passive"))
      (node (ref "C47") (pin "2") (pinfunction "2_2") (pintype "passive"))
      (node (ref "C48") (pin "2") (pinfunction "2_2") (pintype "passive"))
      (node (ref "C49") (pin "2") (pinfunction "2_2") (pintype "passive"))
      (node (ref "U53") (pin "8") (pinfunction "VCC_8") (pintype "passive"))
      (node (ref "U54") (pin "8") (pinfunction "VCC_8") (pintype "passive"))
      (node (ref "U55") (pin "8") (pinfunction "VCC_8") (pintype "passive"))
      (node (ref "U56") (pin "8") (pinfunction "VCC_8") (pintype "passive"))
    )
    (net (code "75") (name "DAC_AVEE") (class "Default")
      (node (ref "C50") (pin "2") (pinfunction "2_2") (pintype "passive"))
      (node (ref "C51") (pin "2") (pinfunction "2_2") (pintype "passive"))
      (node (ref "C52") (pin "2") (pinfunction "2_2") (pintype "passive"))
      (node (ref "C53") (pin "2") (pinfunction "2_2") (pintype "passive"))
      (node (ref "C54") (pin "2") (pinfunction "2_2") (pintype "passive"))
      (node (ref "C55") (pin "2") (pinfunction "2_2") (pintype "passive"))
      (node (ref "C56") (pin "2") (pinfunction "2_2") (pintype "passive"))
      (node (ref "C57") (pin "2") (pinfunction "2_2") (pintype "passive"))
      (node (ref "U53") (pin "4") (pinfunction "GND_4") (pintype "passive"))
      (node (ref "U54") (pin "4") (pinfunction "GND_4") (pintype "passive"))
      (node (ref "U55") (pin "4") (pinfunction "GND_4") (pintype "passive"))
      (node (ref "U56") (pin "4") (pinfunction "GND_4") (pintype "passive"))
    )
    (net (code "76") (name "DAC_D3V3") (class "Default")
      (node (ref "C34") (pin "2") (pinfunction "2_2") (pintype "passive"))
      (node (ref "C35") (pin "2") (pinfunction "2_2") (pintype "passive"))
      (node (ref "C36") (pin "2") (pinfunction "2_2") (pintype "passive"))
      (node (ref "C37") (pin "2") (pinfunction "2_2") (pintype "passive"))
      (node (ref "C38") (pin "2") (pinfunction "2_2") (pintype "passive"))
      (node (ref "C39") (pin "2") (pinfunction "2_2") (pintype "passive"))
      (node (ref "C40") (pin "2") (pinfunction "2_2") (pintype "passive"))
      (node (ref "C41") (pin "2") (pinfunction "2_2") (pintype "passive"))
      (node (ref "R49") (pin "2") (pinfunction "2_2") (pintype "passive"))
      (node (ref "R51") (pin "2") (pinfunction "2_2") (pintype "passive"))
      (node (ref "R70") (pin "2") (pinfunction "2_2") (pintype "passive"))
      (node (ref "R74") (pin "2") (pinfunction "2_2") (pintype "passive"))
      (node (ref "U49") (pin "11") (pinfunction "CLKVDD_11") (pintype "passive"))
      (node (ref "U49") (pin "15") (pinfunction "CMODE_15") (pintype "passive"))
      (node (ref "U49") (pin "3") (pinfunction "DVDD_3") (pintype "passive"))
      (node (ref "U50") (pin "11") (pinfunction "CLKVDD_11") (pintype "passive"))
      (node (ref "U50") (pin "15") (pinfunction "CMODE_15") (pintype "passive"))
      (node (ref "U50") (pin "3") (pinfunction "DVDD_3") (pintype "passive"))
      (node (ref "U51") (pin "11") (pinfunction "CLKVDD_11") (pintype "passive"))
      (node (ref "U51") (pin "15") (pinfunction "CMODE_15") (pintype "passive"))
      (node (ref "U51") (pin "3") (pinfunction "DVDD_3") (pintype "passive"))
      (node (ref "U52") (pin "11") (pinfunction "CLKVDD_11") (pintype "passive"))
      (node (ref "U52") (pin "15") (pinfunction "CMODE_15") (pintype "passive"))
      (node (ref "U52") (pin "3") (pinfunction "DVDD_3") (pintype "passive"))
    )
    (net (code "77") (name "GND") (class "Default")
      (node (ref "C26") (pin "2") (pinfunction "2_2") (pintype "passive"))
      (node (ref "C27") (pin "2") (pinfunction "2_2") (pintype "passive"))
      (node (ref "C28") (pin "2") (pinfunction "2_2") (pintype "passive"))
      (node (ref "C29") (pin "2") (pinfunction "2_2") (pintype "passive"))
      (node (ref "C30") (pin "1") (pinfunction "1_1") (pintype "passive"))
      (node (ref "C31") (pin "1") (pinfunction "1_1") (pintype "passive"))
      (node (ref "C32") (pin "1") (pinfunction "1_1") (pintype "passive"))
      (node (ref "C33") (pin "1") (pinfunction "1_1") (pintype "passive"))
      (node (ref "C34") (pin "1") (pinfunction "1_1") (pintype "passive"))
      (node (ref "C35") (pin "1") (pinfunction "1_1") (pintype "passive"))
      (node (ref "C36") (pin "1") (pinfunction "1_1") (pintype "passive"))
      (node (ref "C37") (pin "1") (pinfunction "1_1") (pintype "passive"))
      (node (ref "C38") (pin "1") (pinfunction "1_1") (pintype "passive"))
      (node (ref "C39") (pin "1") (pinfunction "1_1") (pintype "passive"))
      (node (ref "C40") (pin "1") (pinfunction "1_1") (pintype "passive"))
      (node (ref "C41") (pin "1") (pinfunction "1_1") (pintype "passive"))
      (node (ref "C42") (pin "1") (pinfunction "1_1") (pintype "passive"))
      (node (ref "C43") (pin "1") (pinfunction "1_1") (pintype "passive"))
      (node (ref "C44") (pin "1") (pinfunction "1_1") (pintype "passive"))
      (node (ref "C45") (pin "1") (pinfunction "1_1") (pintype "passive"))
      (node (ref "C46") (pin "1") (pinfunction "1_1") (pintype "passive"))
      (node (ref "C47") (pin "1") (pinfunction "1_1") (pintype "passive"))
      (node (ref "C48") (pin "1") (pinfunction "1_1") (pintype "passive"))
      (node (ref "C49") (pin "1") (pinfunction "1_1") (pintype "passive"))
      (node (ref "C50") (pin "1") (pinfunction "1_1") (pintype "passive"))
      (node (ref "C51") (pin "1") (pinfunction "1_1") (pintype "passive"))
      (node (ref "C52") (pin "1") (pinfunction "1_1") (pintype "passive"))
      (node (ref "C53") (pin "1") (pinfunction "1_1") (pintype "passive"))
      (node (ref "C54") (pin "1") (pinfunction "1_1") (pintype "passive"))
      (node (ref "C55") (pin "1") (pinfunction "1_1") (pintype "passive"))
      (node (ref "C56") (pin "1") (pinfunction "1_1") (pintype "passive"))
      (node (ref "C57") (pin "1") (pinfunction "1_1") (pintype "passive"))
      (node (ref "R47") (pin "2") (pinfunction "2_2") (pintype "passive"))
      (node (ref "R48") (pin "2") (pinfunction "2_2") (pintype "passive"))
      (node (ref "R52") (pin "2") (pinfunction "2_2") (pintype "passive"))
      (node (ref "R58") (pin "1") (pinfunction "1_1") (pintype "passive"))
      (node (ref "R59") (pin "2") (pinfunction "2_2") (pintype "passive"))
      (node (ref "R60") (pin "2") (pinfunction "2_2") (pintype "passive"))
      (node (ref "R62") (pin "2") (pinfunction "2_2") (pintype "passive"))
      (node (ref "R66") (pin "2") (pinfunction "2_2") (pintype "passive"))
      (node (ref "R67") (pin "2") (pinfunction "2_2") (pintype "passive"))
      (node (ref "R71") (pin "1") (pinfunction "1_1") (pintype "passive"))
      (node (ref "R72") (pin "2") (pinfunction "2_2") (pintype "passive"))
      (node (ref "R73") (pin "2") (pinfunction "2_2") (pintype "passive"))
      (node (ref "R76") (pin "2") (pinfunction "2_2") (pintype "passive"))
      (node (ref "R82") (pin "1") (pinfunction "1_1") (pintype "passive"))
      (node (ref "R83") (pin "2") (pinfunction "2_2") (pintype "passive"))
      (node (ref "R84") (pin "2") (pinfunction "2_2") (pintype "passive"))
      (node (ref "R86") (pin "2") (pinfunction "2_2") (pintype "passive"))
      (node (ref "R92") (pin "1") (pinfunction "1_1") (pintype "passive"))
      (node (ref "R93") (pin "2") (pinfunction "2_2") (pintype "passive"))
      (node (ref "R94") (pin "2") (pinfunction "2_2") (pintype "passive"))
      (node (ref "U19") (pin "1") (pinfunction "1_1") (pintype "passive"))
      (node (ref "U19") (pin "2") (pinfunction "2_2") (pintype "passive"))
      (node (ref "U19") (pin "3") (pinfunction "3_3") (pintype "passive"))
      (node (ref "U19") (pin "4") (pinfunction "4_4") (pintype "passive"))
      (node (ref "U20") (pin "1") (pinfunction "1_1") (pintype "passive"))
      (node (ref "U20") (pin "2") (pinfunction "2_2") (pintype "passive"))
      (node (ref "U20") (pin "3") (pinfunction "3_3") (pintype "passive"))
      (node (ref "U20") (pin "4") (pinfunction "4_4") (pintype "passive"))
      (node (ref "U21") (pin "1") (pinfunction "1_1") (pintype "passive"))
      (node (ref "U21") (pin "2") (pinfunction "2_2") (pintype "passive"))
      (node (ref "U21") (pin "3") (pinfunction "3_3") (pintype "passive"))
      (node (ref "U21") (pin "4") (pinfunction "4_4") (pintype "passive"))
      (node (ref "U22") (pin "1") (pinfunction "1_1") (pintype "passive"))
      (node (ref "U22") (pin "2") (pinfunction "2_2") (pintype "passive"))
      (node (ref "U22") (pin "3") (pinfunction "3_3") (pintype "passive"))
      (node (ref "U22") (pin "4") (pinfunction "4_4") (pintype "passive"))
      (node (ref "U49") (pin "10") (pinfunction "DCOM_10") (pintype "passive"))
      (node (ref "U49") (pin "14") (pinfunction "CLKCOM_14") (pintype "passive"))
      (node (ref "U49") (pin "19") (pinfunction "ACOM_19") (pintype "passive"))
      (node (ref "U49") (pin "22") (pinfunction "ACOM_22") (pintype "passive"))
      (node (ref "U49") (pin "25") (pinfunction "SLEEP_25") (pintype "passive"))
      (node (ref "U49") (pin "26") (pinfunction "DCOM_26") (pintype "passive"))
      (node (ref "U49") (pin "33") (pinfunction "EP_33") (pintype "passive"))
      (node (ref "U50") (pin "10") (pinfunction "DCOM_10") (pintype "passive"))
      (node (ref "U50") (pin "14") (pinfunction "CLKCOM_14") (pintype "passive"))
      (node (ref "U50") (pin "19") (pinfunction "ACOM_19") (pintype "passive"))
      (node (ref "U50") (pin "22") (pinfunction "ACOM_22") (pintype "passive"))
      (node (ref "U50") (pin "25") (pinfunction "SLEEP_25") (pintype "passive"))
      (node (ref "U50") (pin "26") (pinfunction "DCOM_26") (pintype "passive"))
      (node (ref "U50") (pin "33") (pinfunction "EP_33") (pintype "passive"))
      (node (ref "U51") (pin "10") (pinfunction "DCOM_10") (pintype "passive"))
      (node (ref "U51") (pin "14") (pinfunction "CLKCOM_14") (pintype "passive"))
      (node (ref "U51") (pin "19") (pinfunction "ACOM_19") (pintype "passive"))
      (node (ref "U51") (pin "22") (pinfunction "ACOM_22") (pintype "passive"))
      (node (ref "U51") (pin "25") (pinfunction "SLEEP_25") (pintype "passive"))
      (node (ref "U51") (pin "26") (pinfunction "DCOM_26") (pintype "passive"))
      (node (ref "U51") (pin "33") (pinfunction "EP_33") (pintype "passive"))
      (node (ref "U52") (pin "10") (pinfunction "DCOM_10") (pintype "passive"))
      (node (ref "U52") (pin "14") (pinfunction "CLKCOM_14") (pintype "passive"))
      (node (ref "U52") (pin "19") (pinfunction "ACOM_19") (pintype "passive"))
      (node (ref "U52") (pin "22") (pinfunction "ACOM_22") (pintype "passive"))
      (node (ref "U52") (pin "25") (pinfunction "SLEEP_25") (pintype "passive"))
      (node (ref "U52") (pin "26") (pinfunction "DCOM_26") (pintype "passive"))
      (node (ref "U52") (pin "33") (pinfunction "EP_33") (pintype "passive"))
    )
    (net (code "78") (name "Net-(R57-Pad2)") (class "Default")
      (node (ref "R57") (pin "2") (pinfunction "2_2") (pintype "passive"))
      (node (ref "U19") (pin "5") (pinfunction "5_5") (pintype "passive"))
    )
    (net (code "79") (name "Net-(R69-Pad2)") (class "Default")
      (node (ref "R69") (pin "2") (pinfunction "2_2") (pintype "passive"))
      (node (ref "U20") (pin "5") (pinfunction "5_5") (pintype "passive"))
    )
    (net (code "80") (name "Net-(R80-Pad2)") (class "Default")
      (node (ref "R80") (pin "2") (pinfunction "2_2") (pintype "passive"))
      (node (ref "U21") (pin "5") (pinfunction "5_5") (pintype "passive"))
    )
    (net (code "81") (name "Net-(R91-Pad2)") (class "Default")
      (node (ref "R91") (pin "2") (pinfunction "2_2") (pintype "passive"))
      (node (ref "U22") (pin "5") (pinfunction "5_5") (pintype "passive"))
    )
    (net (code "82") (name "Net-(U49B-FSADJ)") (class "Default")
      (node (ref "R47") (pin "1") (pinfunction "1_1") (pintype "passive"))
      (node (ref "U49") (pin "24") (pinfunction "FSADJ_24") (pintype "passive"))
    )
    (net (code "83") (name "Net-(U49B-MODE)") (class "Default")
      (node (ref "R49") (pin "1") (pinfunction "1_1") (pintype "passive"))
      (node (ref "U49") (pin "16") (pinfunction "MODE_16") (pintype "passive"))
    )
    (net (code "84") (name "Net-(U49B-REFIO)") (class "Default")
      (node (ref "C26") (pin "1") (pinfunction "1_1") (pintype "passive"))
      (node (ref "U49") (pin "23") (pinfunction "REFIO_23") (pintype "passive"))
    )
    (net (code "85") (name "Net-(U50B-FSADJ)") (class "Default")
      (node (ref "R48") (pin "1") (pinfunction "1_1") (pintype "passive"))
      (node (ref "U50") (pin "24") (pinfunction "FSADJ_24") (pintype "passive"))
    )
    (net (code "86") (name "Net-(U50B-MODE)") (class "Default")
      (node (ref "R51") (pin "1") (pinfunction "1_1") (pintype "passive"))
      (node (ref "U50") (pin "16") (pinfunction "MODE_16") (pintype "passive"))
    )
    (net (code "87") (name "Net-(U50B-REFIO)") (class "Default")
      (node (ref "C27") (pin "1") (pinfunction "1_1") (pintype "passive"))
      (node (ref "U50") (pin "23") (pinfunction "REFIO_23") (pintype "passive"))
    )
    (net (code "88") (name "Net-(U51B-FSADJ)") (class "Default")
      (node (ref "R66") (pin "1") (pinfunction "1_1") (pintype "passive"))
      (node (ref "U51") (pin "24") (pinfunction "FSADJ_24") (pintype "passive"))
    )
    (net (code "89") (name "Net-(U51B-MODE)") (class "Default")
      (node (ref "R74") (pin "1") (pinfunction "1_1") (pintype "passive"))
      (node (ref "U51") (pin "16") (pinfunction "MODE_16") (pintype "passive"))
    )
    (net (code "90") (name "Net-(U51B-REFIO)") (class "Default")
      (node (ref "C29") (pin "1") (pinfunction "1_1") (pintype "passive"))
      (node (ref "U51") (pin "23") (pinfunction "REFIO_23") (pintype "passive"))
    )
    (net (code "91") (name "Net-(U52B-FSADJ)") (class "Default")
      (node (ref "R67") (pin "1") (pinfunction "1_1") (pintype "passive"))
      (node (ref "U52") (pin "24") (pinfunction "FSADJ_24") (pintype "passive"))
    )
    (net (code "92") (name "Net-(U52B-MODE)") (class "Default")
      (node (ref "R70") (pin "1") (pinfunction "1_1") (pintype "passive"))
      (node (ref "U52") (pin "16") (pinfunction "MODE_16") (pintype "passive"))
    )
    (net (code "93") (name "Net-(U52B-REFIO)") (class "Default")
      (node (ref "C28") (pin "1") (pinfunction "1_1") (pintype "passive"))
      (node (ref "U52") (pin "23") (pinfunction "REFIO_23") (pintype "passive"))
    )
    (net (code "94") (name "Net-(U53A-IN1+)") (class "Default")
      (node (ref "R56") (pin "1") (pinfunction "1_1") (pintype "passive"))
      (node (ref "R59") (pin "1") (pinfunction "1_1") (pintype "passive"))
      (node (ref "U53") (pin "3") (pinfunction "IN1+_3") (pintype "passive"))
    )
    (net (code "95") (name "Net-(U53A-IN1-)") (class "Default")
      (node (ref "R50") (pin "2") (pinfunction "2_2") (pintype "passive"))
      (node (ref "R54") (pin "1") (pinfunction "1_1") (pintype "passive"))
      (node (ref "U53") (pin "2") (pinfunction "IN1-_2") (pintype "passive"))
    )
    (net (code "96") (name "Net-(U53A-OUT1)") (class "Default")
      (node (ref "R50") (pin "1") (pinfunction "1_1") (pintype "passive"))
      (node (ref "R55") (pin "2") (pinfunction "2_2") (pintype "passive"))
      (node (ref "U53") (pin "1") (pinfunction "OUT1_1") (pintype "passive"))
    )
    (net (code "97") (name "Net-(U53B-IN2+)") (class "Default")
      (node (ref "R60") (pin "1") (pinfunction "1_1") (pintype "passive"))
      (node (ref "U53") (pin "5") (pinfunction "IN2+_5") (pintype "passive"))
    )
    (net (code "98") (name "Net-(U53B-IN2-)") (class "Default")
      (node (ref "R53") (pin "2") (pinfunction "2_2") (pintype "passive"))
      (node (ref "R55") (pin "1") (pinfunction "1_1") (pintype "passive"))
      (node (ref "U53") (pin "6") (pinfunction "IN2-_6") (pintype "passive"))
    )
    (net (code "99") (name "Net-(U53B-OUT2)") (class "Default")
      (node (ref "R53") (pin "1") (pinfunction "1_1") (pintype "passive"))
      (node (ref "R57") (pin "1") (pinfunction "1_1") (pintype "passive"))
      (node (ref "U53") (pin "7") (pinfunction "OUT2_7") (pintype "passive"))
    )
    (net (code "100") (name "Net-(U54A-IN1+)") (class "Default")
      (node (ref "R68") (pin "1") (pinfunction "1_1") (pintype "passive"))
      (node (ref "R72") (pin "1") (pinfunction "1_1") (pintype "passive"))
      (node (ref "U54") (pin "3") (pinfunction "IN1+_3") (pintype "passive"))
    )
    (net (code "101") (name "Net-(U54A-IN1-)") (class "Default")
      (node (ref "R61") (pin "2") (pinfunction "2_2") (pintype "passive"))
      (node (ref "R64") (pin "1") (pinfunction "1_1") (pintype "passive"))
      (node (ref "U54") (pin "2") (pinfunction "IN1-_2") (pintype "passive"))
    )
    (net (code "102") (name "Net-(U54A-OUT1)") (class "Default")
      (node (ref "R61") (pin "1") (pinfunction "1_1") (pintype "passive"))
      (node (ref "R65") (pin "2") (pinfunction "2_2") (pintype "passive"))
      (node (ref "U54") (pin "1") (pinfunction "OUT1_1") (pintype "passive"))
    )
    (net (code "103") (name "Net-(U54B-IN2+)") (class "Default")
      (node (ref "R73") (pin "1") (pinfunction "1_1") (pintype "passive"))
      (node (ref "U54") (pin "5") (pinfunction "IN2+_5") (pintype "passive"))
    )
    (net (code "104") (name "Net-(U54B-IN2-)") (class "Default")
      (node (ref "R63") (pin "2") (pinfunction "2_2") (pintype "passive"))
      (node (ref "R65") (pin "1") (pinfunction "1_1") (pintype "passive"))
      (node (ref "U54") (pin "6") (pinfunction "IN2-_6") (pintype "passive"))
    )
    (net (code "105") (name "Net-(U54B-OUT2)") (class "Default")
      (node (ref "R63") (pin "1") (pinfunction "1_1") (pintype "passive"))
      (node (ref "R69") (pin "1") (pinfunction "1_1") (pintype "passive"))
      (node (ref "U54") (pin "7") (pinfunction "OUT2_7") (pintype "passive"))
    )
    (net (code "106") (name "Net-(U55A-IN1+)") (class "Default")
      (node (ref "R81") (pin "1") (pinfunction "1_1") (pintype "passive"))
      (node (ref "R83") (pin "1") (pinfunction "1_1") (pintype "passive"))
      (node (ref "U55") (pin "3") (pinfunction "IN1+_3") (pintype "passive"))
    )
    (net (code "107") (name "Net-(U55A-IN1-)") (class "Default")
      (node (ref "R75") (pin "2") (pinfunction "2_2") (pintype "passive"))
      (node (ref "R78") (pin "1") (pinfunction "1_1") (pintype "passive"))
      (node (ref "U55") (pin "2") (pinfunction "IN1-_2") (pintype "passive"))
    )
    (net (code "108") (name "Net-(U55A-OUT1)") (class "Default")
      (node (ref "R75") (pin "1") (pinfunction "1_1") (pintype "passive"))
      (node (ref "R79") (pin "2") (pinfunction "2_2") (pintype "passive"))
      (node (ref "U55") (pin "1") (pinfunction "OUT1_1") (pintype "passive"))
    )
    (net (code "109") (name "Net-(U55B-IN2+)") (class "Default")
      (node (ref "R84") (pin "1") (pinfunction "1_1") (pintype "passive"))
      (node (ref "U55") (pin "5") (pinfunction "IN2+_5") (pintype "passive"))
    )
    (net (code "110") (name "Net-(U55B-IN2-)") (class "Default")
      (node (ref "R77") (pin "2") (pinfunction "2_2") (pintype "passive"))
      (node (ref "R79") (pin "1") (pinfunction "1_1") (pintype "passive"))
      (node (ref "U55") (pin "6") (pinfunction "IN2-_6") (pintype "passive"))
    )
    (net (code "111") (name "Net-(U55B-OUT2)") (class "Default")
      (node (ref "R77") (pin "1") (pinfunction "1_1") (pintype "passive"))
      (node (ref "R80") (pin "1") (pinfunction "1_1") (pintype "passive"))
      (node (ref "U55") (pin "7") (pinfunction "OUT2_7") (pintype "passive"))
    )
    (net (code "112") (name "Net-(U56A-IN1+)") (class "Default")
      (node (ref "R90") (pin "1") (pinfunction "1_1") (pintype "passive"))
      (node (ref "R93") (pin "1") (pinfunction "1_1") (pintype "passive"))
      (node (ref "U56") (pin "3") (pinfunction "IN1+_3") (pintype "passive"))
    )
    (net (code "113") (name "Net-(U56A-IN1-)") (class "Default")
      (node (ref "R85") (pin "2") (pinfunction "2_2") (pintype "passive"))
      (node (ref "R88") (pin "1") (pinfunction "1_1") (pintype "passive"))
      (node (ref "U56") (pin "2") (pinfunction "IN1-_2") (pintype "passive"))
    )
    (net (code "114") (name "Net-(U56A-OUT1)") (class "Default")
      (node (ref "R85") (pin "1") (pinfunction "1_1") (pintype "passive"))
      (node (ref "R89") (pin "2") (pinfunction "2_2") (pintype "passive"))
      (node (ref "U56") (pin "1") (pinfunction "OUT1_1") (pintype "passive"))
    )
    (net (code "115") (name "Net-(U56B-IN2+)") (class "Default")
      (node (ref "R94") (pin "1") (pinfunction "1_1") (pintype "passive"))
      (node (ref "U56") (pin "5") (pinfunction "IN2+_5") (pintype "passive"))
    )
    (net (code "116") (name "Net-(U56B-IN2-)") (class "Default")
      (node (ref "R87") (pin "2") (pinfunction "2_2") (pintype "passive"))
      (node (ref "R89") (pin "1") (pinfunction "1_1") (pintype "passive"))
      (node (ref "U56") (pin "6") (pinfunction "IN2-_6") (pintype "passive"))
    )
    (net (code "117") (name "Net-(U56B-OUT2)") (class "Default")
      (node (ref "R87") (pin "1") (pinfunction "1_1") (pintype "passive"))
      (node (ref "R91") (pin "1") (pinfunction "1_1") (pintype "passive"))
      (node (ref "U56") (pin "7") (pinfunction "OUT2_7") (pintype "passive"))
    )
  )
)
